# Sheet1.net
KiCad netlist of a schematic drawn in Altium Designer
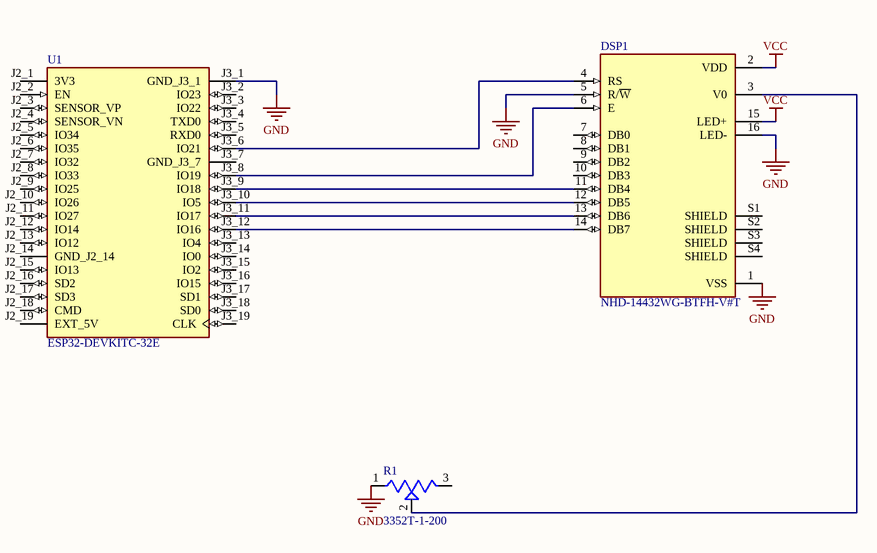
[diagram p0: Sheet1.SchDoc]

(export (version "E")
  (design (tool "Eeschema 10.0.6"))
  (components
    (comp (ref "DSP1")
      (value "NHD-14432WG-BTFH-V#T")
      (footprint "LCD_NHD-14432WG-BTFH-V#T")
      (fields (field (name "MF") "Newhaven Display"))
      (libsource (lib "NHD-14432WG-BTFH-V#T") (part "NHD-14432WG-BTFH-V#T"))
    )
    (comp (ref "R1")
      (value "3352T-1-200")
      (footprint "TRIM_3352T-1-200")
      (description "20 Ohms 0.5W, 1/2W Through Hole Thumbwheel Potentiometer Top Adjustment")
      (fields (field (name "MF") "Bourns"))
      (libsource (lib "3352T-1-200") (part "3352T-1-200"))
    )
    (comp (ref "U1")
      (value "ESP32-DEVKITC-32E")
      (footprint "MODULE_ESP32-DEVKITC-32E")
      (fields (field (name "MF") "Espressif Systems"))
      (libsource (lib "ESP32-DEVKITC-32E") (part "ESP32-DEVKITC-32E"))
    )
  )
  (nets
    (net (code "1") (name "GND") (class "Default")
      (node (ref "DSP1") (pin "1") (pinfunction "VSS_1") (pintype "power_in"))
      (node (ref "DSP1") (pin "16") (pinfunction "LED-_16") (pintype "passive"))
      (node (ref "DSP1") (pin "5") (pinfunction "R/~{W}_5") (pintype "input"))
      (node (ref "R1") (pin "1") (pinfunction "CCW_1") (pintype "passive"))
      (node (ref "U1") (pin "J3_1") (pinfunction "GND_J3_1_J3_1") (pintype "power_in"))
    )
    (net (code "2") (name "Net-(DSP1-DB4)") (class "Default")
      (node (ref "DSP1") (pin "11") (pinfunction "DB4_11") (pintype "bidirectional"))
      (node (ref "U1") (pin "J3_9") (pinfunction "IO18_J3_9") (pintype "bidirectional"))
    )
    (net (code "3") (name "Net-(DSP1-DB5)") (class "Default")
      (node (ref "DSP1") (pin "12") (pinfunction "DB5_12") (pintype "bidirectional"))
      (node (ref "U1") (pin "J3_10") (pinfunction "IO5_J3_10") (pintype "bidirectional"))
    )
    (net (code "4") (name "Net-(DSP1-DB6)") (class "Default")
      (node (ref "DSP1") (pin "13") (pinfunction "DB6_13") (pintype "bidirectional"))
      (node (ref "U1") (pin "J3_11") (pinfunction "IO17_J3_11") (pintype "bidirectional"))
    )
    (net (code "5") (name "Net-(DSP1-DB7)") (class "Default")
      (node (ref "DSP1") (pin "14") (pinfunction "DB7_14") (pintype "bidirectional"))
      (node (ref "U1") (pin "J3_12") (pinfunction "IO16_J3_12") (pintype "bidirectional"))
    )
    (net (code "6") (name "Net-(DSP1-E)") (class "Default")
      (node (ref "DSP1") (pin "6") (pinfunction "E_6") (pintype "input"))
      (node (ref "U1") (pin "J3_8") (pinfunction "IO19_J3_8") (pintype "bidirectional"))
    )
    (net (code "7") (name "Net-(DSP1-RS)") (class "Default")
      (node (ref "DSP1") (pin "4") (pinfunction "RS_4") (pintype "input"))
      (node (ref "U1") (pin "J3_6") (pinfunction "IO21_J3_6") (pintype "bidirectional"))
    )
    (net (code "8") (name "Net-(DSP1-V0)") (class "Default")
      (node (ref "DSP1") (pin "3") (pinfunction "V0_3") (pintype "passive"))
      (node (ref "R1") (pin "2") (pinfunction "WIPER_2") (pintype "passive"))
    )
    (net (code "9") (name "VCC") (class "Default")
      (node (ref "DSP1") (pin "15") (pinfunction "LED+_15") (pintype "passive"))
      (node (ref "DSP1") (pin "2") (pinfunction "VDD_2") (pintype "power_in"))
    )
    (net (code "10") (name "unconnected-(DSP1-DB0-Pad7)") (class "Default")
      (node (ref "DSP1") (pin "7") (pinfunction "DB0_7") (pintype "bidirectional"))
    )
    (net (code "11") (name "unconnected-(DSP1-DB1-Pad8)") (class "Default")
      (node (ref "DSP1") (pin "8") (pinfunction "DB1_8") (pintype "bidirectional"))
    )
    (net (code "12") (name "unconnected-(DSP1-DB2-Pad9)") (class "Default")
      (node (ref "DSP1") (pin "9") (pinfunction "DB2_9") (pintype "bidirectional"))
    )
    (net (code "13") (name "unconnected-(DSP1-DB3-Pad10)") (class "Default")
      (node (ref "DSP1") (pin "10") (pinfunction "DB3_10") (pintype "bidirectional"))
    )
    (net (code "14") (name "unconnected-(DSP1-SHIELD-PadS1)") (class "Default")
      (node (ref "DSP1") (pin "S1") (pinfunction "SHIELD_S1") (pintype "passive"))
    )
    (net (code "15") (name "unconnected-(DSP1-SHIELD-PadS2)") (class "Default")
      (node (ref "DSP1") (pin "S2") (pinfunction "SHIELD_S2") (pintype "passive"))
    )
    (net (code "16") (name "unconnected-(DSP1-SHIELD-PadS3)") (class "Default")
      (node (ref "DSP1") (pin "S3") (pinfunction "SHIELD_S3") (pintype "passive"))
    )
    (net (code "17") (name "unconnected-(DSP1-SHIELD-PadS4)") (class "Default")
      (node (ref "DSP1") (pin "S4") (pinfunction "SHIELD_S4") (pintype "passive"))
    )
    (net (code "18") (name "unconnected-(R1-CW-Pad3)") (class "Default")
      (node (ref "R1") (pin "3") (pinfunction "CW_3") (pintype "passive"))
    )
    (net (code "19") (name "unconnected-(U1-3V3-PadJ2_1)") (class "Default")
      (node (ref "U1") (pin "J2_1") (pinfunction "3V3_J2_1") (pintype "power_in"))
    )
    (net (code "20") (name "unconnected-(U1-CLK-PadJ3_19)") (class "Default")
      (node (ref "U1") (pin "J3_19") (pinfunction "CLK_J3_19") (pintype "bidirectional"))
    )
    (net (code "21") (name "unconnected-(U1-CMD-PadJ2_18)") (class "Default")
      (node (ref "U1") (pin "J2_18") (pinfunction "CMD_J2_18") (pintype "bidirectional"))
    )
    (net (code "22") (name "unconnected-(U1-EN-PadJ2_2)") (class "Default")
      (node (ref "U1") (pin "J2_2") (pinfunction "EN_J2_2") (pintype "input"))
    )
    (net (code "23") (name "unconnected-(U1-EXT_5V-PadJ2_19)") (class "Default")
      (node (ref "U1") (pin "J2_19") (pinfunction "EXT_5V_J2_19") (pintype "power_in"))
    )
    (net (code "24") (name "unconnected-(U1-GND_J2_14-PadJ2_14)") (class "Default")
      (node (ref "U1") (pin "J2_14") (pinfunction "GND_J2_14_J2_14") (pintype "power_in"))
    )
    (net (code "25") (name "unconnected-(U1-GND_J3_7-PadJ3_7)") (class "Default")
      (node (ref "U1") (pin "J3_7") (pinfunction "GND_J3_7_J3_7") (pintype "power_in"))
    )
    (net (code "26") (name "unconnected-(U1-IO0-PadJ3_14)") (class "Default")
      (node (ref "U1") (pin "J3_14") (pinfunction "IO0_J3_14") (pintype "bidirectional"))
    )
    (net (code "27") (name "unconnected-(U1-IO2-PadJ3_15)") (class "Default")
      (node (ref "U1") (pin "J3_15") (pinfunction "IO2_J3_15") (pintype "bidirectional"))
    )
    (net (code "28") (name "unconnected-(U1-IO4-PadJ3_13)") (class "Default")
      (node (ref "U1") (pin "J3_13") (pinfunction "IO4_J3_13") (pintype "bidirectional"))
    )
    (net (code "29") (name "unconnected-(U1-IO12-PadJ2_13)") (class "Default")
      (node (ref "U1") (pin "J2_13") (pinfunction "IO12_J2_13") (pintype "bidirectional"))
    )
    (net (code "30") (name "unconnected-(U1-IO13-PadJ2_15)") (class "Default")
      (node (ref "U1") (pin "J2_15") (pinfunction "IO13_J2_15") (pintype "bidirectional"))
    )
    (net (code "31") (name "unconnected-(U1-IO14-PadJ2_12)") (class "Default")
      (node (ref "U1") (pin "J2_12") (pinfunction "IO14_J2_12") (pintype "bidirectional"))
    )
    (net (code "32") (name "unconnected-(U1-IO15-PadJ3_16)") (class "Default")
      (node (ref "U1") (pin "J3_16") (pinfunction "IO15_J3_16") (pintype "bidirectional"))
    )
    (net (code "33") (name "unconnected-(U1-IO22-PadJ3_3)") (class "Default")
      (node (ref "U1") (pin "J3_3") (pinfunction "IO22_J3_3") (pintype "bidirectional"))
    )
    (net (code "34") (name "unconnected-(U1-IO23-PadJ3_2)") (class "Default")
      (node (ref "U1") (pin "J3_2") (pinfunction "IO23_J3_2") (pintype "bidirectional"))
    )
    (net (code "35") (name "unconnected-(U1-IO25-PadJ2_9)") (class "Default")
      (node (ref "U1") (pin "J2_9") (pinfunction "IO25_J2_9") (pintype "bidirectional"))
    )
    (net (code "36") (name "unconnected-(U1-IO26-PadJ2_10)") (class "Default")
      (node (ref "U1") (pin "J2_10") (pinfunction "IO26_J2_10") (pintype "bidirectional"))
    )
    (net (code "37") (name "unconnected-(U1-IO27-PadJ2_11)") (class "Default")
      (node (ref "U1") (pin "J2_11") (pinfunction "IO27_J2_11") (pintype "bidirectional"))
    )
    (net (code "38") (name "unconnected-(U1-IO32-PadJ2_7)") (class "Default")
      (node (ref "U1") (pin "J2_7") (pinfunction "IO32_J2_7") (pintype "bidirectional"))
    )
    (net (code "39") (name "unconnected-(U1-IO33-PadJ2_8)") (class "Default")
      (node (ref "U1") (pin "J2_8") (pinfunction "IO33_J2_8") (pintype "bidirectional"))
    )
    (net (code "40") (name "unconnected-(U1-IO34-PadJ2_5)") (class "Default")
      (node (ref "U1") (pin "J2_5") (pinfunction "IO34_J2_5") (pintype "bidirectional"))
    )
    (net (code "41") (name "unconnected-(U1-IO35-PadJ2_6)") (class "Default")
      (node (ref "U1") (pin "J2_6") (pinfunction "IO35_J2_6") (pintype "bidirectional"))
    )
    (net (code "42") (name "unconnected-(U1-RXD0-PadJ3_5)") (class "Default")
      (node (ref "U1") (pin "J3_5") (pinfunction "RXD0_J3_5") (pintype "bidirectional"))
    )
    (net (code "43") (name "unconnected-(U1-SD0-PadJ3_18)") (class "Default")
      (node (ref "U1") (pin "J3_18") (pinfunction "SD0_J3_18") (pintype "bidirectional"))
    )
    (net (code "44") (name "unconnected-(U1-SD1-PadJ3_17)") (class "Default")
      (node (ref "U1") (pin "J3_17") (pinfunction "SD1_J3_17") (pintype "bidirectional"))
    )
    (net (code "45") (name "unconnected-(U1-SD2-PadJ2_16)") (class "Default")
      (node (ref "U1") (pin "J2_16") (pinfunction "SD2_J2_16") (pintype "bidirectional"))
    )
    (net (code "46") (name "unconnected-(U1-SD3-PadJ2_17)") (class "Default")
      (node (ref "U1") (pin "J2_17") (pinfunction "SD3_J2_17") (pintype "bidirectional"))
    )
    (net (code "47") (name "unconnected-(U1-SENSOR_VN-PadJ2_4)") (class "Default")
      (node (ref "U1") (pin "J2_4") (pinfunction "SENSOR_VN_J2_4") (pintype "bidirectional"))
    )
    (net (code "48") (name "unconnected-(U1-SENSOR_VP-PadJ2_3)") (class "Default")
      (node (ref "U1") (pin "J2_3") (pinfunction "SENSOR_VP_J2_3") (pintype "bidirectional"))
    )
    (net (code "49") (name "unconnected-(U1-TXD0-PadJ3_4)") (class "Default")
      (node (ref "U1") (pin "J3_4") (pinfunction "TXD0_J3_4") (pintype "bidirectional"))
    )
  )
)
